# keyboard_5keys_board_drc_filled.net
KiCad netlist of a schematic drawn in EAGLE
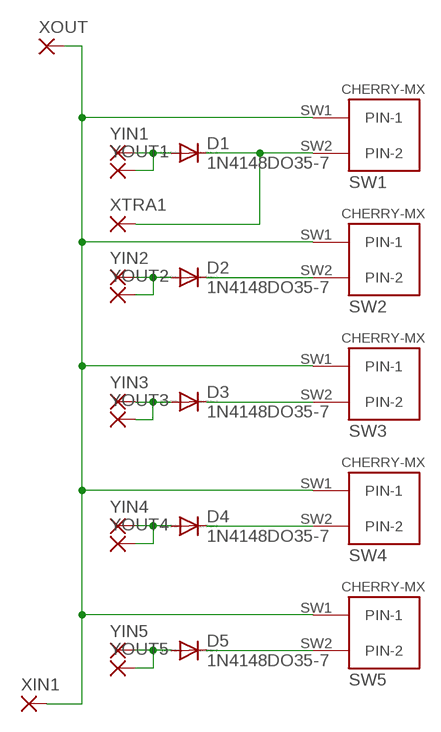
[diagram p0: schematic, sheet 1]

(export (version "E")
  (design (tool "Eeschema 10.0.6"))
  (components
    (comp (ref "D1")
      (value "1N4148DO35-7")
      (footprint "eagle-import:DO35-7")
      (libsource (lib "eagle-import") (part "1N4148DO35-7"))
    )
    (comp (ref "D2")
      (value "1N4148DO35-7")
      (footprint "eagle-import:DO35-7")
      (libsource (lib "eagle-import") (part "1N4148DO35-7"))
    )
    (comp (ref "D3")
      (value "1N4148DO35-7")
      (footprint "eagle-import:DO35-7")
      (libsource (lib "eagle-import") (part "1N4148DO35-7"))
    )
    (comp (ref "D4")
      (value "1N4148DO35-7")
      (footprint "eagle-import:DO35-7")
      (libsource (lib "eagle-import") (part "1N4148DO35-7"))
    )
    (comp (ref "D5")
      (value "1N4148DO35-7")
      (footprint "eagle-import:DO35-7")
      (libsource (lib "eagle-import") (part "1N4148DO35-7"))
    )
    (comp (ref "SW1")
      (value "CHERRY-MX")
      (footprint "eagle-import:CHERRY-MX")
      (libsource (lib "eagle-import") (part "CHERRY-MX"))
    )
    (comp (ref "SW2")
      (value "CHERRY-MX")
      (footprint "eagle-import:CHERRY-MX")
      (libsource (lib "eagle-import") (part "CHERRY-MX"))
    )
    (comp (ref "SW3")
      (value "CHERRY-MX")
      (footprint "eagle-import:CHERRY-MX")
      (libsource (lib "eagle-import") (part "CHERRY-MX"))
    )
    (comp (ref "SW4")
      (value "CHERRY-MX")
      (footprint "eagle-import:CHERRY-MX")
      (libsource (lib "eagle-import") (part "CHERRY-MX"))
    )
    (comp (ref "SW5")
      (value "CHERRY-MX")
      (footprint "eagle-import:CHERRY-MX")
      (libsource (lib "eagle-import") (part "CHERRY-MX"))
    )
    (comp (ref "XIN1")
      (value "1,6/0,8")
      (footprint "eagle-import:1,6_0,8")
      (libsource (lib "eagle-import") (part "1,6/0,8"))
    )
    (comp (ref "XOUT")
      (value "1,6/0,8")
      (footprint "eagle-import:1,6_0,8")
      (libsource (lib "eagle-import") (part "1,6/0,8"))
    )
    (comp (ref "XTRA1")
      (value "1,6/0,8")
      (footprint "eagle-import:1,6_0,8")
      (libsource (lib "eagle-import") (part "1,6/0,8"))
    )
    (comp (ref "YIN1")
      (value "1,6/0,8")
      (footprint "eagle-import:1,6_0,8")
      (libsource (lib "eagle-import") (part "1,6/0,8"))
    )
    (comp (ref "YIN2")
      (value "1,6/0,8")
      (footprint "eagle-import:1,6_0,8")
      (libsource (lib "eagle-import") (part "1,6/0,8"))
    )
    (comp (ref "YIN3")
      (value "1,6/0,8")
      (footprint "eagle-import:1,6_0,8")
      (libsource (lib "eagle-import") (part "1,6/0,8"))
    )
    (comp (ref "YIN4")
      (value "1,6/0,8")
      (footprint "eagle-import:1,6_0,8")
      (libsource (lib "eagle-import") (part "1,6/0,8"))
    )
    (comp (ref "YIN5")
      (value "1,6/0,8")
      (footprint "eagle-import:1,6_0,8")
      (libsource (lib "eagle-import") (part "1,6/0,8"))
    )
    (comp (ref "YOUT1")
      (value "1,6/0,8")
      (footprint "eagle-import:1,6_0,8")
      (libsource (lib "eagle-import") (part "1,6/0,8"))
    )
    (comp (ref "YOUT2")
      (value "1,6/0,8")
      (footprint "eagle-import:1,6_0,8")
      (libsource (lib "eagle-import") (part "1,6/0,8"))
    )
    (comp (ref "YOUT3")
      (value "1,6/0,8")
      (footprint "eagle-import:1,6_0,8")
      (libsource (lib "eagle-import") (part "1,6/0,8"))
    )
    (comp (ref "YOUT4")
      (value "1,6/0,8")
      (footprint "eagle-import:1,6_0,8")
      (libsource (lib "eagle-import") (part "1,6/0,8"))
    )
    (comp (ref "YOUT5")
      (value "1,6/0,8")
      (footprint "eagle-import:1,6_0,8")
      (libsource (lib "eagle-import") (part "1,6/0,8"))
    )
  )
  (nets
    (net (code "1") (name "Net-(SW1-PIN-1)") (class "Default")
      (node (ref "SW1") (pin "SW1") (pinfunction "PIN-1_SW1") (pintype "bidirectional"))
      (node (ref "SW2") (pin "SW1") (pinfunction "PIN-1_SW1") (pintype "bidirectional"))
      (node (ref "SW3") (pin "SW1") (pinfunction "PIN-1_SW1") (pintype "bidirectional"))
      (node (ref "SW4") (pin "SW1") (pinfunction "PIN-1_SW1") (pintype "bidirectional"))
      (node (ref "SW5") (pin "SW1") (pinfunction "PIN-1_SW1") (pintype "bidirectional"))
      (node (ref "XIN1") (pin "1") (pinfunction "P_1") (pintype "passive"))
      (node (ref "XOUT") (pin "1") (pinfunction "P_1") (pintype "passive"))
    )
    (net (code "2") (name "Net-(SW1-PIN-2)") (class "Default")
      (node (ref "D1") (pin "C") (pinfunction "C_C") (pintype "passive"))
      (node (ref "SW1") (pin "SW2") (pinfunction "PIN-2_SW2") (pintype "bidirectional"))
      (node (ref "XTRA1") (pin "1") (pinfunction "P_1") (pintype "passive"))
    )
    (net (code "3") (name "Net-(SW2-PIN-2)") (class "Default")
      (node (ref "D2") (pin "C") (pinfunction "C_C") (pintype "passive"))
      (node (ref "SW2") (pin "SW2") (pinfunction "PIN-2_SW2") (pintype "bidirectional"))
    )
    (net (code "4") (name "Net-(SW3-PIN-2)") (class "Default")
      (node (ref "D3") (pin "C") (pinfunction "C_C") (pintype "passive"))
      (node (ref "SW3") (pin "SW2") (pinfunction "PIN-2_SW2") (pintype "bidirectional"))
    )
    (net (code "5") (name "Net-(SW4-PIN-2)") (class "Default")
      (node (ref "D4") (pin "C") (pinfunction "C_C") (pintype "passive"))
      (node (ref "SW4") (pin "SW2") (pinfunction "PIN-2_SW2") (pintype "bidirectional"))
    )
    (net (code "6") (name "Net-(SW5-PIN-2)") (class "Default")
      (node (ref "D5") (pin "C") (pinfunction "C_C") (pintype "passive"))
      (node (ref "SW5") (pin "SW2") (pinfunction "PIN-2_SW2") (pintype "bidirectional"))
    )
    (net (code "7") (name "Net-(YIN1-P)") (class "Default")
      (node (ref "D1") (pin "A") (pinfunction "A_A") (pintype "passive"))
      (node (ref "YIN1") (pin "1") (pinfunction "P_1") (pintype "passive"))
      (node (ref "YOUT1") (pin "1") (pinfunction "P_1") (pintype "passive"))
    )
    (net (code "8") (name "Net-(YIN2-P)") (class "Default")
      (node (ref "D2") (pin "A") (pinfunction "A_A") (pintype "passive"))
      (node (ref "YIN2") (pin "1") (pinfunction "P_1") (pintype "passive"))
      (node (ref "YOUT2") (pin "1") (pinfunction "P_1") (pintype "passive"))
    )
    (net (code "9") (name "Net-(YIN3-P)") (class "Default")
      (node (ref "D3") (pin "A") (pinfunction "A_A") (pintype "passive"))
      (node (ref "YIN3") (pin "1") (pinfunction "P_1") (pintype "passive"))
      (node (ref "YOUT3") (pin "1") (pinfunction "P_1") (pintype "passive"))
    )
    (net (code "10") (name "Net-(YIN4-P)") (class "Default")
      (node (ref "D4") (pin "A") (pinfunction "A_A") (pintype "passive"))
      (node (ref "YIN4") (pin "1") (pinfunction "P_1") (pintype "passive"))
      (node (ref "YOUT4") (pin "1") (pinfunction "P_1") (pintype "passive"))
    )
    (net (code "11") (name "Net-(YIN5-P)") (class "Default")
      (node (ref "D5") (pin "A") (pinfunction "A_A") (pintype "passive"))
      (node (ref "YIN5") (pin "1") (pinfunction "P_1") (pintype "passive"))
      (node (ref "YOUT5") (pin "1") (pinfunction "P_1") (pintype "passive"))
    )
  )
)
